# Schematics.net
KiCad netlist of a schematic drawn in EAGLE
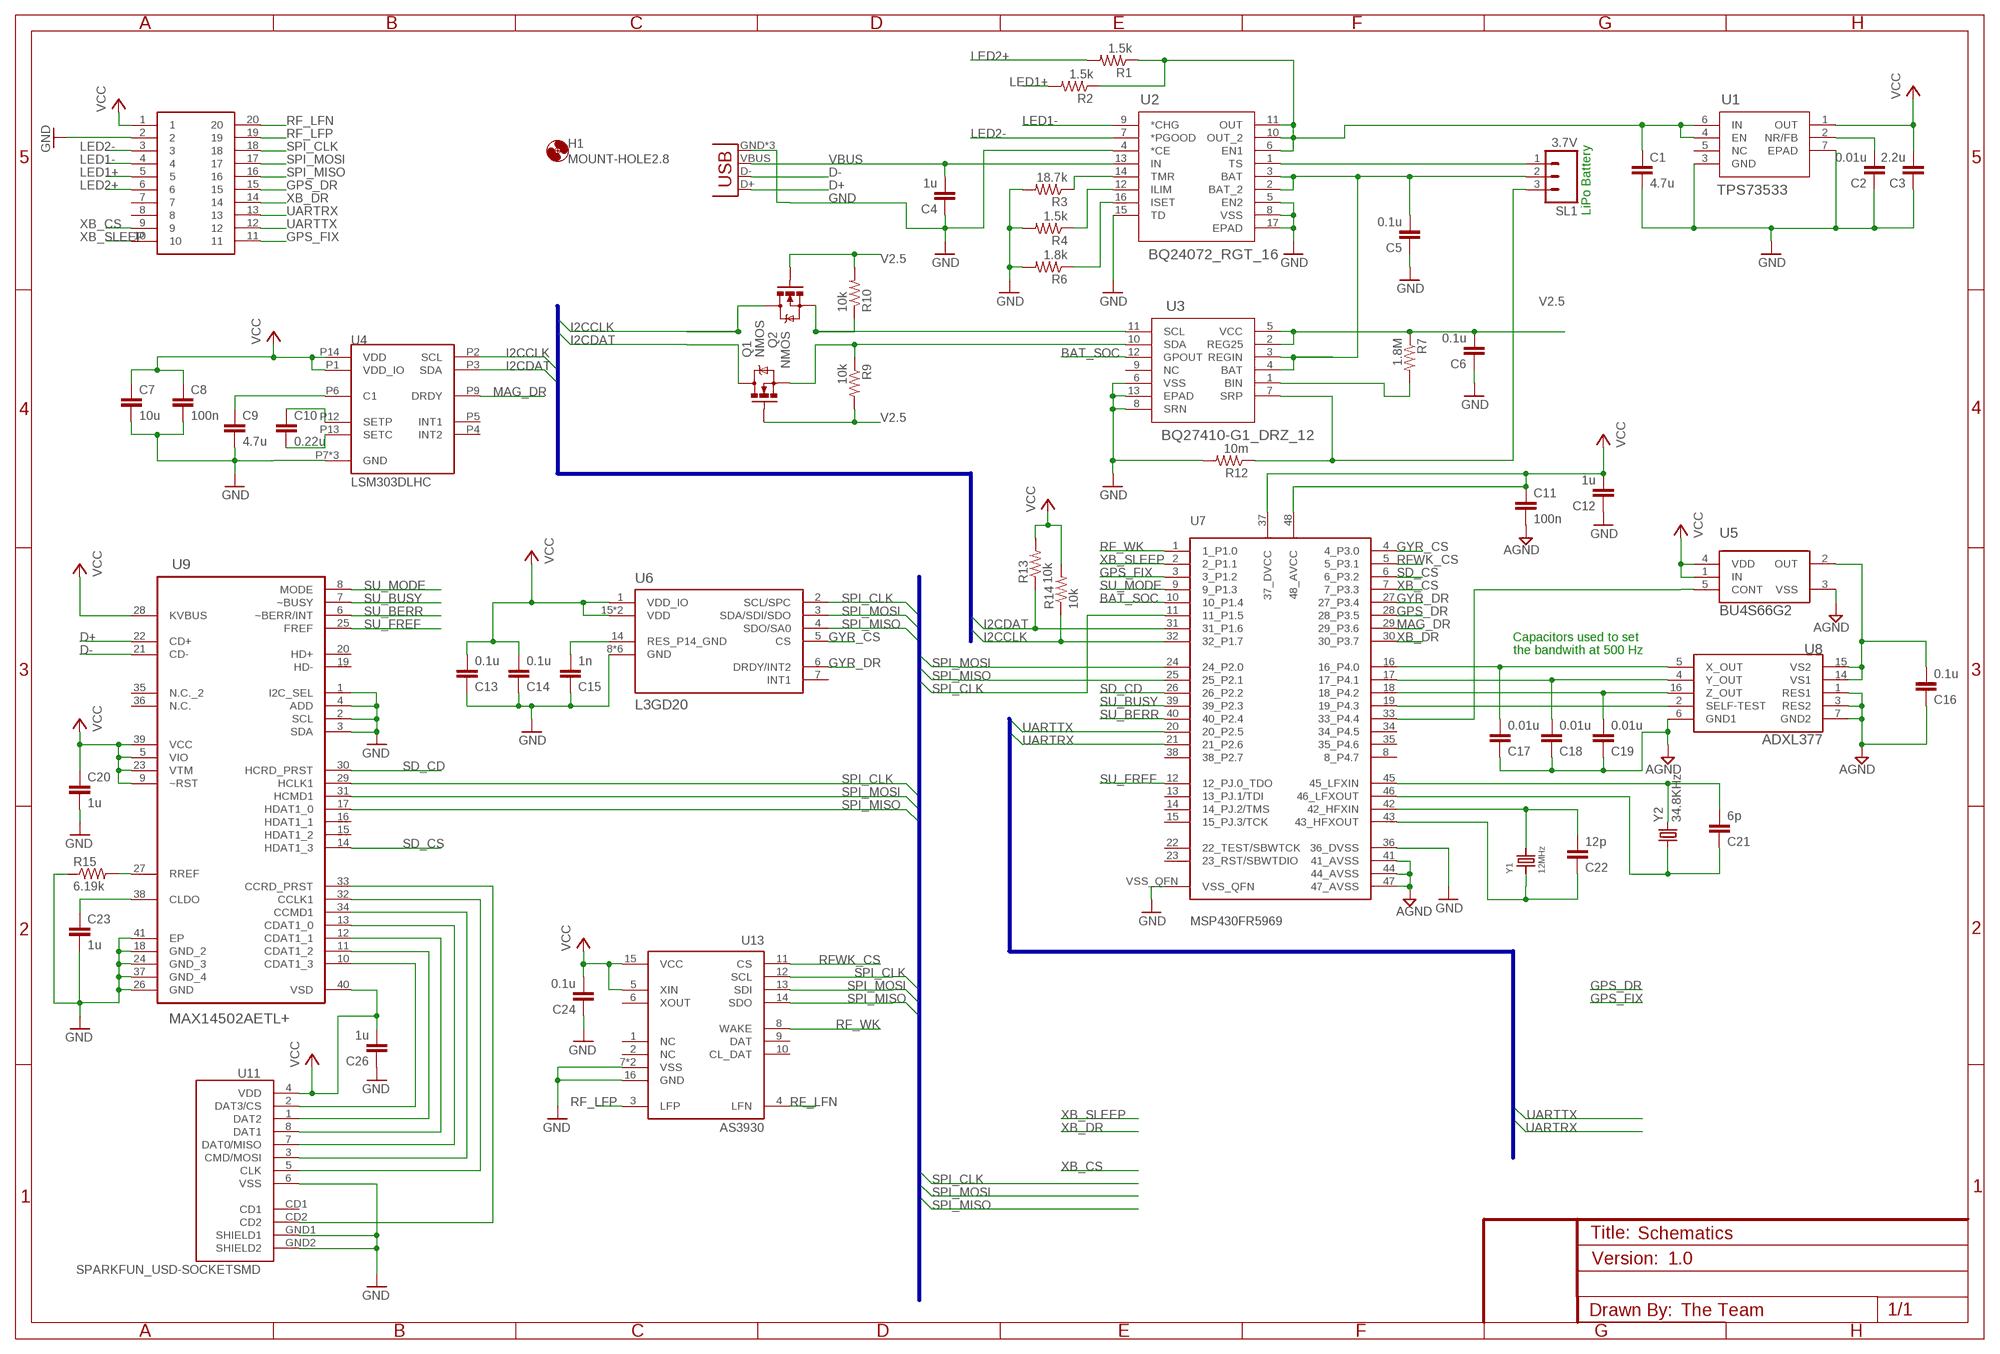
[diagram p0: schematic, sheet 1]

(export (version "E")
  (design (tool "Eeschema 10.0.6"))
  (components
    (comp (ref "C1")
      (value "4.7u")
      (footprint "eagle-import:C0603")
      (libsource (lib "eagle-import") (part "C-EUC0603"))
    )
    (comp (ref "C2")
      (value "0.01u")
      (footprint "eagle-import:C0603")
      (libsource (lib "eagle-import") (part "C-EUC0603"))
    )
    (comp (ref "C3")
      (value "2.2u")
      (footprint "eagle-import:C0603")
      (libsource (lib "eagle-import") (part "C-EUC0603"))
    )
    (comp (ref "C4")
      (value "1u")
      (footprint "eagle-import:C0603")
      (libsource (lib "eagle-import") (part "C-EUC0603"))
    )
    (comp (ref "C5")
      (value "0.1u")
      (footprint "eagle-import:C0603")
      (libsource (lib "eagle-import") (part "C-EUC0603"))
    )
    (comp (ref "C6")
      (value "0.1u")
      (footprint "eagle-import:C0603")
      (libsource (lib "eagle-import") (part "C-EUC0603"))
    )
    (comp (ref "C7")
      (value "10u")
      (footprint "eagle-import:C0603")
      (libsource (lib "eagle-import") (part "C-EUC0603"))
    )
    (comp (ref "C8")
      (value "100n")
      (footprint "eagle-import:C0603")
      (libsource (lib "eagle-import") (part "C-EUC0603"))
    )
    (comp (ref "C9")
      (value "4.7u")
      (footprint "eagle-import:C0603")
      (libsource (lib "eagle-import") (part "C-EUC0603"))
    )
    (comp (ref "C10")
      (value "0.22u")
      (footprint "eagle-import:C0603")
      (libsource (lib "eagle-import") (part "C-EUC0603"))
    )
    (comp (ref "C11")
      (value "100n")
      (footprint "eagle-import:C0603")
      (libsource (lib "eagle-import") (part "C-EUC0603"))
    )
    (comp (ref "C12")
      (value "1u")
      (footprint "eagle-import:C0603")
      (libsource (lib "eagle-import") (part "C-EUC0603"))
    )
    (comp (ref "C13")
      (value "0.1u")
      (footprint "eagle-import:C0603")
      (libsource (lib "eagle-import") (part "C-EUC0603"))
    )
    (comp (ref "C14")
      (value "0.1u")
      (footprint "eagle-import:C0603")
      (libsource (lib "eagle-import") (part "C-EUC0603"))
    )
    (comp (ref "C15")
      (value "1n")
      (footprint "eagle-import:C0603")
      (libsource (lib "eagle-import") (part "C-EUC0603"))
    )
    (comp (ref "C16")
      (value "0.1u")
      (footprint "eagle-import:C0603")
      (libsource (lib "eagle-import") (part "C-EUC0603"))
    )
    (comp (ref "C17")
      (value "0.01u")
      (footprint "eagle-import:C0603")
      (libsource (lib "eagle-import") (part "C-EUC0603"))
    )
    (comp (ref "C18")
      (value "0.01u")
      (footprint "eagle-import:C0603")
      (libsource (lib "eagle-import") (part "C-EUC0603"))
    )
    (comp (ref "C19")
      (value "0.01u")
      (footprint "eagle-import:C0603")
      (libsource (lib "eagle-import") (part "C-EUC0603"))
    )
    (comp (ref "C20")
      (value "1u")
      (footprint "eagle-import:C0603")
      (libsource (lib "eagle-import") (part "C-EUC0603"))
    )
    (comp (ref "C21")
      (value "6p")
      (footprint "eagle-import:C0603")
      (libsource (lib "eagle-import") (part "C-EUC0603"))
    )
    (comp (ref "C22")
      (value "12p")
      (footprint "eagle-import:C0603")
      (libsource (lib "eagle-import") (part "C-EUC0603"))
    )
    (comp (ref "C23")
      (value "1u")
      (footprint "eagle-import:C0603")
      (libsource (lib "eagle-import") (part "C-EUC0603"))
    )
    (comp (ref "C24")
      (value "0.1u")
      (footprint "eagle-import:C0603")
      (libsource (lib "eagle-import") (part "C-EUC0603"))
    )
    (comp (ref "C26")
      (value "1u")
      (footprint "eagle-import:C0603")
      (libsource (lib "eagle-import") (part "C-EUC0603"))
    )
    (comp (ref "H1")
      (value "MOUNT-HOLE2.8")
      (footprint "eagle-import:2,8")
      (libsource (lib "eagle-import") (part "MOUNT-HOLE2.8"))
    )
    (comp (ref "JP1")
      (value "USB-MICROB")
      (footprint "eagle-import:USB-MICROB")
      (libsource (lib "eagle-import") (part "USB-MICROB"))
    )
    (comp (ref "Q1")
      (value "NMOS")
      (footprint "eagle-import:SOT23")
      (libsource (lib "eagle-import") (part "MOSFET-NCHANNELBSS138"))
    )
    (comp (ref "Q2")
      (value "NMOS")
      (footprint "eagle-import:SOT23")
      (libsource (lib "eagle-import") (part "MOSFET-NCHANNELBSS138"))
    )
    (comp (ref "R1")
      (value "1.5k")
      (footprint "eagle-import:R0603")
      (libsource (lib "eagle-import") (part "R-US_R0603"))
    )
    (comp (ref "R2")
      (value "1.5k")
      (footprint "eagle-import:R0603")
      (libsource (lib "eagle-import") (part "R-US_R0603"))
    )
    (comp (ref "R3")
      (value "18.7k")
      (footprint "eagle-import:R0603")
      (libsource (lib "eagle-import") (part "R-US_R0603"))
    )
    (comp (ref "R4")
      (value "1.5k")
      (footprint "eagle-import:R0603")
      (libsource (lib "eagle-import") (part "R-US_R0603"))
    )
    (comp (ref "R6")
      (value "1.8k")
      (footprint "eagle-import:R0603")
      (libsource (lib "eagle-import") (part "R-US_R0603"))
    )
    (comp (ref "R7")
      (value "1.8M")
      (footprint "eagle-import:R0603")
      (libsource (lib "eagle-import") (part "R-US_R0603"))
    )
    (comp (ref "R9")
      (value "10k")
      (footprint "eagle-import:R0603")
      (libsource (lib "eagle-import") (part "R-US_R0603"))
    )
    (comp (ref "R10")
      (value "10k")
      (footprint "eagle-import:R0603")
      (libsource (lib "eagle-import") (part "R-US_R0603"))
    )
    (comp (ref "R12")
      (value "10m")
      (footprint "eagle-import:R0603")
      (libsource (lib "eagle-import") (part "R-US_R0603"))
    )
    (comp (ref "R13")
      (value "10k")
      (footprint "eagle-import:R0603")
      (libsource (lib "eagle-import") (part "R-US_R0603"))
    )
    (comp (ref "R14")
      (value "10k")
      (footprint "eagle-import:R0603")
      (libsource (lib "eagle-import") (part "R-US_R0603"))
    )
    (comp (ref "R15")
      (value "6.19k")
      (footprint "eagle-import:R0603")
      (libsource (lib "eagle-import") (part "R-US_R0603"))
    )
    (comp (ref "SL1")
      (value "3.7V")
      (footprint "eagle-import:03P")
      (libsource (lib "eagle-import") (part "M03"))
    )
    (comp (ref "U$1")
      (value "20-SOCKET")
      (footprint "eagle-import:20-SOCKET")
      (libsource (lib "eagle-import") (part "20-SOCKET"))
    )
    (comp (ref "U1")
      (value "TPS73533")
      (footprint "eagle-import:DRV6_1P6X1")
      (fields
        (field (name "MANUFACTURER") "Texas Instruments")
        (field (name "MANUFACTURER_PART_NUMBER") "tps73533_drv_6")
      )
      (libsource (lib "eagle-import") (part "TPS73533_DRV_6"))
    )
    (comp (ref "U2")
      (value "BQ24072_RGT_16")
      (footprint "eagle-import:RGT16_1P7X1P7")
      (fields
        (field (name "GENERIC_PART_NUMBER") "BQ24072")
        (field (name "MANUFACTURER") "Texas Instruments")
      )
      (libsource (lib "eagle-import") (part "BQ24072_RGT_16"))
    )
    (comp (ref "U3")
      (value "BQ27410-G1_DRZ_12")
      (footprint "eagle-import:DRZ12_1P95X2P45")
      (fields
        (field (name "GENERIC_PART_NUMBER") "BQ27410-G1")
        (field (name "MANUFACTURER") "Texas Instruments")
      )
      (libsource (lib "eagle-import") (part "BQ27410-G1_DRZ_12"))
    )
    (comp (ref "U4")
      (value "LSM303DLHC")
      (footprint "eagle-import:LGA_3X5X1_14L")
      (libsource (lib "eagle-import") (part "LSM303DLHC"))
    )
    (comp (ref "U5")
      (value "BU4S66G2")
      (footprint "eagle-import:SSOP5")
      (libsource (lib "eagle-import") (part "BU4S66G2"))
    )
    (comp (ref "U6")
      (value "L3GD20")
      (footprint "eagle-import:L3GD20")
      (libsource (lib "eagle-import") (part "L3GD20"))
    )
    (comp (ref "U7")
      (value "MSP430FR5969")
      (footprint "eagle-import:RGZ(S-PQFP-N48)")
      (libsource (lib "eagle-import") (part "MSP430FR5969"))
    )
    (comp (ref "U8")
      (value "ADXL377")
      (footprint "eagle-import:LFCSP-16")
      (libsource (lib "eagle-import") (part "ADXL377"))
    )
    (comp (ref "U9")
      (value "MAX14502AETL+")
      (footprint "eagle-import:QFN40P500X500X80-41N")
      (libsource (lib "eagle-import") (part "MAX14502AETL+"))
    )
    (comp (ref "U11")
      (value "SPARKFUN_USD-SOCKETSMD")
      (footprint "eagle-import:SPARKFUN_MICRO-SD-SOCKET-PP")
      (libsource (lib "eagle-import") (part "SPARKFUN_USD-SOCKETSMD"))
    )
    (comp (ref "U13")
      (value "AS3930")
      (footprint "eagle-import:AS3930")
      (libsource (lib "eagle-import") (part "AS3930"))
    )
    (comp (ref "Y1")
      (value "12MHz")
      (footprint "eagle-import:3.2X2.5MM")
      (libsource (lib "eagle-import") (part "CRYSTAL"))
    )
    (comp (ref "Y2")
      (value "34.8KHz")
      (footprint "eagle-import:TC38H")
      (libsource (lib "eagle-import") (part "CRYSTALTC38H"))
    )
  )
  (nets
    (net (code "1") (name "/BAT_SOC") (class "Default")
      (node (ref "U3") (pin "12") (pinfunction "GPOUT_12") (pintype "output"))
      (node (ref "U7") (pin "10") (pinfunction "10_P1.4_10") (pintype "bidirectional"))
    )
    (net (code "2") (name "/D+") (class "Default")
      (node (ref "JP1") (pin "D+") (pinfunction "D+_D+") (pintype "bidirectional"))
      (node (ref "U9") (pin "22") (pinfunction "CD+_22") (pintype "passive"))
    )
    (net (code "3") (name "/D-") (class "Default")
      (node (ref "JP1") (pin "D-") (pinfunction "D-_D-") (pintype "bidirectional"))
      (node (ref "U9") (pin "21") (pinfunction "CD-_21") (pintype "passive"))
    )
    (net (code "4") (name "/GPS_DR") (class "Default")
      (node (ref "U$1") (pin "15") (pinfunction "15_15") (pintype "bidirectional"))
      (node (ref "U7") (pin "28") (pinfunction "28_P3.5_28") (pintype "bidirectional"))
    )
    (net (code "5") (name "/GPS_FIX") (class "Default")
      (node (ref "U$1") (pin "11") (pinfunction "11_11") (pintype "bidirectional"))
      (node (ref "U7") (pin "3") (pinfunction "3_P1.2_3") (pintype "bidirectional"))
    )
    (net (code "6") (name "/GYR_CS") (class "Default")
      (node (ref "U6") (pin "5") (pinfunction "CS_5") (pintype "input"))
      (node (ref "U7") (pin "4") (pinfunction "4_P3.0_4") (pintype "bidirectional"))
    )
    (net (code "7") (name "/GYR_DR") (class "Default")
      (node (ref "U6") (pin "6") (pinfunction "DRDY/INT2_6") (pintype "output"))
      (node (ref "U7") (pin "27") (pinfunction "27_P3.4_27") (pintype "bidirectional"))
    )
    (net (code "8") (name "/I2CCLK") (class "Default")
      (node (ref "Q2") (pin "3") (pinfunction "D_3") (pintype "passive"))
      (node (ref "R14") (pin "1") (pinfunction "1_1") (pintype "passive"))
      (node (ref "U4") (pin "P2") (pinfunction "SCL_P2") (pintype "bidirectional"))
      (node (ref "U7") (pin "32") (pinfunction "32_P1.7_32") (pintype "bidirectional"))
    )
    (net (code "9") (name "/I2CDAT") (class "Default")
      (node (ref "Q1") (pin "3") (pinfunction "D_3") (pintype "passive"))
      (node (ref "R13") (pin "1") (pinfunction "1_1") (pintype "passive"))
      (node (ref "U4") (pin "P3") (pinfunction "SDA_P3") (pintype "bidirectional"))
      (node (ref "U7") (pin "31") (pinfunction "31_P1.6_31") (pintype "bidirectional"))
    )
    (net (code "10") (name "/LED1+") (class "Default")
      (node (ref "R2") (pin "2") (pinfunction "2_2") (pintype "passive"))
      (node (ref "U$1") (pin "5") (pinfunction "5_5") (pintype "bidirectional"))
    )
    (net (code "11") (name "/LED1-") (class "Default")
      (node (ref "U$1") (pin "4") (pinfunction "4_4") (pintype "bidirectional"))
      (node (ref "U2") (pin "9") (pinfunction "*CHG_9") (pintype "output"))
    )
    (net (code "12") (name "/LED2+") (class "Default")
      (node (ref "R1") (pin "2") (pinfunction "2_2") (pintype "passive"))
      (node (ref "U$1") (pin "6") (pinfunction "6_6") (pintype "bidirectional"))
    )
    (net (code "13") (name "/LED2-") (class "Default")
      (node (ref "U$1") (pin "3") (pinfunction "3_3") (pintype "bidirectional"))
      (node (ref "U2") (pin "7") (pinfunction "*PGOOD_7") (pintype "output"))
    )
    (net (code "14") (name "/MAG_DR") (class "Default")
      (node (ref "U4") (pin "P9") (pinfunction "DRDY_P9") (pintype "bidirectional"))
      (node (ref "U7") (pin "29") (pinfunction "29_P3.6_29") (pintype "bidirectional"))
    )
    (net (code "15") (name "/RFWK_CS") (class "Default")
      (node (ref "U13") (pin "11") (pinfunction "CS_11") (pintype "bidirectional"))
      (node (ref "U7") (pin "5") (pinfunction "5_P3.1_5") (pintype "bidirectional"))
    )
    (net (code "16") (name "/RF_LFN") (class "Default")
      (node (ref "U$1") (pin "20") (pinfunction "20_20") (pintype "bidirectional"))
      (node (ref "U13") (pin "4") (pinfunction "LFN_4") (pintype "bidirectional"))
    )
    (net (code "17") (name "/RF_LFP") (class "Default")
      (node (ref "U$1") (pin "19") (pinfunction "19_19") (pintype "bidirectional"))
      (node (ref "U13") (pin "3") (pinfunction "LFP_3") (pintype "bidirectional"))
    )
    (net (code "18") (name "/RF_WK") (class "Default")
      (node (ref "U13") (pin "8") (pinfunction "WAKE_8") (pintype "bidirectional"))
      (node (ref "U7") (pin "1") (pinfunction "1_P1.0_1") (pintype "bidirectional"))
    )
    (net (code "19") (name "/SD_CD") (class "Default")
      (node (ref "U7") (pin "26") (pinfunction "26_P2.2_26") (pintype "bidirectional"))
      (node (ref "U9") (pin "30") (pinfunction "HCRD_PRST_30") (pintype "passive"))
    )
    (net (code "20") (name "/SD_CS") (class "Default")
      (node (ref "U7") (pin "6") (pinfunction "6_P3.2_6") (pintype "bidirectional"))
      (node (ref "U9") (pin "14") (pinfunction "HDAT1_3_14") (pintype "passive"))
    )
    (net (code "21") (name "/SPI_CLK") (class "Default")
      (node (ref "U$1") (pin "18") (pinfunction "18_18") (pintype "bidirectional"))
      (node (ref "U13") (pin "12") (pinfunction "SCL_12") (pintype "bidirectional"))
      (node (ref "U6") (pin "2") (pinfunction "SCL/SPC_2") (pintype "input"))
      (node (ref "U7") (pin "11") (pinfunction "11_P1.5_11") (pintype "bidirectional"))
      (node (ref "U9") (pin "29") (pinfunction "HCLK1_29") (pintype "input"))
    )
    (net (code "22") (name "/SPI_MISO") (class "Default")
      (node (ref "U$1") (pin "16") (pinfunction "16_16") (pintype "bidirectional"))
      (node (ref "U13") (pin "14") (pinfunction "SDO_14") (pintype "bidirectional"))
      (node (ref "U6") (pin "4") (pinfunction "SDO/SA0_4") (pintype "bidirectional"))
      (node (ref "U7") (pin "25") (pinfunction "25_P2.1_25") (pintype "bidirectional"))
      (node (ref "U9") (pin "17") (pinfunction "HDAT1_0_17") (pintype "passive"))
    )
    (net (code "23") (name "/SPI_MOSI") (class "Default")
      (node (ref "U$1") (pin "17") (pinfunction "17_17") (pintype "bidirectional"))
      (node (ref "U13") (pin "13") (pinfunction "SDI_13") (pintype "bidirectional"))
      (node (ref "U6") (pin "3") (pinfunction "SDA/SDI/SDO_3") (pintype "bidirectional"))
      (node (ref "U7") (pin "24") (pinfunction "24_P2.0_24") (pintype "bidirectional"))
      (node (ref "U9") (pin "31") (pinfunction "HCMD1_31") (pintype "passive"))
    )
    (net (code "24") (name "/SU_BERR") (class "Default")
      (node (ref "U7") (pin "40") (pinfunction "40_P2.4_40") (pintype "bidirectional"))
      (node (ref "U9") (pin "6") (pinfunction "~{BERR/INT}_6") (pintype "bidirectional"))
    )
    (net (code "25") (name "/SU_BUSY") (class "Default")
      (node (ref "U7") (pin "39") (pinfunction "39_P2.3_39") (pintype "bidirectional"))
      (node (ref "U9") (pin "7") (pinfunction "~{BUSY}_7") (pintype "output"))
    )
    (net (code "26") (name "/SU_FREF") (class "Default")
      (node (ref "U7") (pin "12") (pinfunction "12_PJ.0_TDO_12") (pintype "bidirectional"))
      (node (ref "U9") (pin "25") (pinfunction "FREF_25") (pintype "passive"))
    )
    (net (code "27") (name "/SU_MODE") (class "Default")
      (node (ref "U7") (pin "9") (pinfunction "9_P1.3_9") (pintype "bidirectional"))
      (node (ref "U9") (pin "8") (pinfunction "MODE_8") (pintype "input"))
    )
    (net (code "28") (name "/UARTRX") (class "Default")
      (node (ref "U$1") (pin "13") (pinfunction "13_13") (pintype "bidirectional"))
      (node (ref "U7") (pin "21") (pinfunction "21_P2.6_21") (pintype "bidirectional"))
    )
    (net (code "29") (name "/UARTTX") (class "Default")
      (node (ref "U$1") (pin "12") (pinfunction "12_12") (pintype "bidirectional"))
      (node (ref "U7") (pin "20") (pinfunction "20_P2.5_20") (pintype "bidirectional"))
    )
    (net (code "30") (name "/V2.5") (class "Default")
      (node (ref "C6") (pin "2") (pinfunction "2_2") (pintype "passive"))
      (node (ref "Q1") (pin "1") (pinfunction "G_1") (pintype "passive"))
      (node (ref "Q2") (pin "1") (pinfunction "G_1") (pintype "passive"))
      (node (ref "R10") (pin "2") (pinfunction "2_2") (pintype "passive"))
      (node (ref "R7") (pin "1") (pinfunction "1_1") (pintype "passive"))
      (node (ref "R9") (pin "2") (pinfunction "2_2") (pintype "passive"))
      (node (ref "U3") (pin "2") (pinfunction "REG25_2") (pintype "power_in"))
      (node (ref "U3") (pin "5") (pinfunction "VCC_5") (pintype "power_in"))
    )
    (net (code "31") (name "/VBUS") (class "Default")
      (node (ref "C4") (pin "2") (pinfunction "2_2") (pintype "passive"))
      (node (ref "JP1") (pin "VBUS") (pinfunction "VBUS_VBUS") (pintype "bidirectional"))
      (node (ref "U2") (pin "13") (pinfunction "IN_13") (pintype "input"))
    )
    (net (code "32") (name "/XB_CS") (class "Default")
      (node (ref "U$1") (pin "9") (pinfunction "9_9") (pintype "bidirectional"))
      (node (ref "U7") (pin "7") (pinfunction "7_P3.3_7") (pintype "bidirectional"))
    )
    (net (code "33") (name "/XB_DR") (class "Default")
      (node (ref "U$1") (pin "14") (pinfunction "14_14") (pintype "bidirectional"))
      (node (ref "U7") (pin "30") (pinfunction "30_P3.7_30") (pintype "bidirectional"))
    )
    (net (code "34") (name "/XB_SLEEP") (class "Default")
      (node (ref "U$1") (pin "10") (pinfunction "10_10") (pintype "bidirectional"))
      (node (ref "U7") (pin "2") (pinfunction "2_P1.1_2") (pintype "bidirectional"))
    )
    (net (code "35") (name "AGND") (class "Default")
      (node (ref "C11") (pin "2") (pinfunction "2_2") (pintype "passive"))
      (node (ref "C16") (pin "1") (pinfunction "1_1") (pintype "passive"))
      (node (ref "C17") (pin "1") (pinfunction "1_1") (pintype "passive"))
      (node (ref "C18") (pin "1") (pinfunction "1_1") (pintype "passive"))
      (node (ref "C19") (pin "1") (pinfunction "1_1") (pintype "passive"))
      (node (ref "U5") (pin "3") (pinfunction "VSS_3") (pintype "bidirectional"))
      (node (ref "U7") (pin "41") (pinfunction "41_AVSS_41") (pintype "bidirectional"))
      (node (ref "U7") (pin "44") (pinfunction "44_AVSS_44") (pintype "bidirectional"))
      (node (ref "U7") (pin "47") (pinfunction "47_AVSS_47") (pintype "bidirectional"))
      (node (ref "U8") (pin "1") (pinfunction "RES1_1") (pintype "bidirectional"))
      (node (ref "U8") (pin "3") (pinfunction "RES2_3") (pintype "bidirectional"))
      (node (ref "U8") (pin "6") (pinfunction "GND1_6") (pintype "bidirectional"))
      (node (ref "U8") (pin "7") (pinfunction "GND2_7") (pintype "bidirectional"))
    )
    (net (code "36") (name "GND") (class "Default")
      (node (ref "C1") (pin "2") (pinfunction "2_2") (pintype "passive"))
      (node (ref "C12") (pin "1") (pinfunction "1_1") (pintype "passive"))
      (node (ref "C13") (pin "1") (pinfunction "1_1") (pintype "passive"))
      (node (ref "C14") (pin "1") (pinfunction "1_1") (pintype "passive"))
      (node (ref "C15") (pin "1") (pinfunction "1_1") (pintype "passive"))
      (node (ref "C2") (pin "1") (pinfunction "1_1") (pintype "passive"))
      (node (ref "C20") (pin "2") (pinfunction "2_2") (pintype "passive"))
      (node (ref "C23") (pin "2") (pinfunction "2_2") (pintype "passive"))
      (node (ref "C24") (pin "1") (pinfunction "1_1") (pintype "passive"))
      (node (ref "C26") (pin "1") (pinfunction "1_1") (pintype "passive"))
      (node (ref "C3") (pin "1") (pinfunction "1_1") (pintype "passive"))
      (node (ref "C4") (pin "1") (pinfunction "1_1") (pintype "passive"))
      (node (ref "C5") (pin "1") (pinfunction "1_1") (pintype "passive"))
      (node (ref "C6") (pin "1") (pinfunction "1_1") (pintype "passive"))
      (node (ref "C7") (pin "2") (pinfunction "2_2") (pintype "passive"))
      (node (ref "C8") (pin "2") (pinfunction "2_2") (pintype "passive"))
      (node (ref "C9") (pin "2") (pinfunction "2_2") (pintype "passive"))
      (node (ref "JP1") (pin "GND") (pinfunction "GND_GND") (pintype "bidirectional"))
      (node (ref "JP1") (pin "MT1") (pinfunction "GND_MT1") (pintype "bidirectional"))
      (node (ref "JP1") (pin "MT2") (pinfunction "GND_MT2") (pintype "bidirectional"))
      (node (ref "R12") (pin "2") (pinfunction "2_2") (pintype "passive"))
      (node (ref "R15") (pin "1") (pinfunction "1_1") (pintype "passive"))
      (node (ref "R3") (pin "2") (pinfunction "2_2") (pintype "passive"))
      (node (ref "R4") (pin "2") (pinfunction "2_2") (pintype "passive"))
      (node (ref "R6") (pin "2") (pinfunction "2_2") (pintype "passive"))
      (node (ref "U$1") (pin "2") (pinfunction "2_2") (pintype "bidirectional"))
      (node (ref "U1") (pin "3") (pinfunction "GND_3") (pintype "power_in"))
      (node (ref "U1") (pin "7") (pinfunction "EPAD_7") (pintype "passive"))
      (node (ref "U11") (pin "6") (pinfunction "VSS_6") (pintype "bidirectional"))
      (node (ref "U11") (pin "GND1") (pinfunction "SHIELD1_GND1") (pintype "bidirectional"))
      (node (ref "U11") (pin "GND2") (pinfunction "SHIELD2_GND2") (pintype "bidirectional"))
      (node (ref "U13") (pin "16") (pinfunction "GND_16") (pintype "bidirectional"))
      (node (ref "U13") (pin "7") (pinfunction "VSS_7") (pintype "bidirectional"))
      (node (ref "U13") (pin "EXP") (pinfunction "VSS_EXP") (pintype "bidirectional"))
      (node (ref "U2") (pin "15") (pinfunction "TD_15") (pintype "input"))
      (node (ref "U2") (pin "17") (pinfunction "EPAD_17") (pintype "power_in"))
      (node (ref "U2") (pin "4") (pinfunction "*CE_4") (pintype "input"))
      (node (ref "U2") (pin "5") (pinfunction "EN2_5") (pintype "input"))
      (node (ref "U2") (pin "8") (pinfunction "VSS_8") (pintype "power_in"))
      (node (ref "U3") (pin "13") (pinfunction "EPAD_13") (pintype "power_in"))
      (node (ref "U3") (pin "6") (pinfunction "VSS_6") (pintype "power_in"))
      (node (ref "U3") (pin "8") (pinfunction "SRN_8") (pintype "input"))
      (node (ref "U4") (pin "P10") (pinfunction "GND_P10") (pintype "bidirectional"))
      (node (ref "U4") (pin "P11") (pinfunction "GND_P11") (pintype "bidirectional"))
      (node (ref "U4") (pin "P7") (pinfunction "GND_P7") (pintype "bidirectional"))
      (node (ref "U6") (pin "10") (pinfunction "GND_10") (pintype "bidirectional"))
      (node (ref "U6") (pin "11") (pinfunction "GND_11") (pintype "bidirectional"))
      (node (ref "U6") (pin "12") (pinfunction "GND_12") (pintype "bidirectional"))
      (node (ref "U6") (pin "13") (pinfunction "GND_13") (pintype "bidirectional"))
      (node (ref "U6") (pin "8") (pinfunction "GND_8") (pintype "bidirectional"))
      (node (ref "U6") (pin "9") (pinfunction "GND_9") (pintype "bidirectional"))
      (node (ref "U7") (pin "36") (pinfunction "36_DVSS_36") (pintype "bidirectional"))
      (node (ref "U7") (pin "VSS_QFN") (pinfunction "VSS_QFN_VSS_QFN") (pintype "bidirectional"))
      (node (ref "U9") (pin "1") (pinfunction "I2C_SEL_1") (pintype "input"))
      (node (ref "U9") (pin "18") (pinfunction "GND_2_18") (pintype "passive"))
      (node (ref "U9") (pin "2") (pinfunction "SCL_2") (pintype "input"))
      (node (ref "U9") (pin "24") (pinfunction "GND_3_24") (pintype "passive"))
      (node (ref "U9") (pin "26") (pinfunction "GND_26") (pintype "passive"))
      (node (ref "U9") (pin "3") (pinfunction "SDA_3") (pintype "bidirectional"))
      (node (ref "U9") (pin "37") (pinfunction "GND_4_37") (pintype "passive"))
      (node (ref "U9") (pin "4") (pinfunction "ADD_4") (pintype "input"))
      (node (ref "U9") (pin "41") (pinfunction "EP_41") (pintype "passive"))
    )
    (net (code "37") (name "Net-(Q1-S)") (class "Default")
      (node (ref "Q1") (pin "2") (pinfunction "S_2") (pintype "passive"))
      (node (ref "R9") (pin "1") (pinfunction "1_1") (pintype "passive"))
      (node (ref "U3") (pin "10") (pinfunction "SDA_10") (pintype "bidirectional"))
    )
    (net (code "38") (name "Net-(Q2-S)") (class "Default")
      (node (ref "Q2") (pin "2") (pinfunction "S_2") (pintype "passive"))
      (node (ref "R10") (pin "1") (pinfunction "1_1") (pintype "passive"))
      (node (ref "U3") (pin "11") (pinfunction "SCL_11") (pintype "input"))
    )
    (net (code "39") (name "Net-(U1-EN)") (class "Default")
      (node (ref "C1") (pin "1") (pinfunction "1_1") (pintype "passive"))
      (node (ref "R1") (pin "1") (pinfunction "1_1") (pintype "passive"))
      (node (ref "R2") (pin "1") (pinfunction "1_1") (pintype "passive"))
      (node (ref "U1") (pin "4") (pinfunction "EN_4") (pintype "passive"))
      (node (ref "U1") (pin "6") (pinfunction "IN_6") (pintype "input"))
      (node (ref "U2") (pin "10") (pinfunction "OUT_2_10") (pintype "output"))
      (node (ref "U2") (pin "11") (pinfunction "OUT_11") (pintype "output"))
      (node (ref "U2") (pin "6") (pinfunction "EN1_6") (pintype "input"))
    )
    (net (code "40") (name "Net-(U1-NR{slash}FB)") (class "Default")
      (node (ref "C2") (pin "2") (pinfunction "2_2") (pintype "passive"))
      (node (ref "U1") (pin "2") (pinfunction "NR/FB_2") (pintype "bidirectional"))
    )
    (net (code "41") (name "Net-(U2-BAT)") (class "Default")
      (node (ref "C5") (pin "2") (pinfunction "2_2") (pintype "passive"))
      (node (ref "SL1") (pin "2") (pinfunction "2_2") (pintype "passive"))
      (node (ref "U2") (pin "2") (pinfunction "BAT_2_2") (pintype "bidirectional"))
      (node (ref "U2") (pin "3") (pinfunction "BAT_3") (pintype "bidirectional"))
      (node (ref "U3") (pin "3") (pinfunction "REGIN_3") (pintype "power_in"))
      (node (ref "U3") (pin "4") (pinfunction "BAT_4") (pintype "input"))
    )
    (net (code "42") (name "Net-(U2-ILIM)") (class "Default")
      (node (ref "R4") (pin "1") (pinfunction "1_1") (pintype "passive"))
      (node (ref "U2") (pin "12") (pinfunction "ILIM_12") (pintype "input"))
    )
    (net (code "43") (name "Net-(U2-ISET)") (class "Default")
      (node (ref "R6") (pin "1") (pinfunction "1_1") (pintype "passive"))
      (node (ref "U2") (pin "16") (pinfunction "ISET_16") (pintype "bidirectional"))
    )
    (net (code "44") (name "Net-(U2-TMR)") (class "Default")
      (node (ref "R3") (pin "1") (pinfunction "1_1") (pintype "passive"))
      (node (ref "U2") (pin "14") (pinfunction "TMR_14") (pintype "input"))
    )
    (net (code "45") (name "Net-(U2-TS)") (class "Default")
      (node (ref "SL1") (pin "1") (pinfunction "1_1") (pintype "passive"))
      (node (ref "U2") (pin "1") (pinfunction "TS_1") (pintype "input"))
    )
    (net (code "46") (name "Net-(U3-BIN)") (class "Default")
      (node (ref "R7") (pin "2") (pinfunction "2_2") (pintype "passive"))
      (node (ref "U3") (pin "1") (pinfunction "BIN_1") (pintype "input"))
    )
    (net (code "47") (name "Net-(U3-SRP)") (class "Default")
      (node (ref "R12") (pin "1") (pinfunction "1_1") (pintype "passive"))
      (node (ref "SL1") (pin "3") (pinfunction "3_3") (pintype "passive"))
      (node (ref "U3") (pin "7") (pinfunction "SRP_7") (pintype "input"))
    )
    (net (code "48") (name "Net-(U4-C1)") (class "Default")
      (node (ref "C9") (pin "1") (pinfunction "1_1") (pintype "passive"))
      (node (ref "U4") (pin "P6") (pinfunction "C1_P6") (pintype "bidirectional"))
    )
    (net (code "49") (name "Net-(U4-SETC)") (class "Default")
      (node (ref "C10") (pin "2") (pinfunction "2_2") (pintype "passive"))
      (node (ref "U4") (pin "P13") (pinfunction "SETC_P13") (pintype "bidirectional"))
    )
    (net (code "50") (name "Net-(U4-SETP)") (class "Default")
      (node (ref "C10") (pin "1") (pinfunction "1_1") (pintype "passive"))
      (node (ref "U4") (pin "P12") (pinfunction "SETP_P12") (pintype "bidirectional"))
    )
    (net (code "51") (name "Net-(U5-CONT)") (class "Default")
      (node (ref "U5") (pin "5") (pinfunction "CONT_5") (pintype "bidirectional"))
      (node (ref "U7") (pin "33") (pinfunction "33_P4.4_33") (pintype "bidirectional"))
    )
    (net (code "52") (name "Net-(U5-OUT)") (class "Default")
      (node (ref "C16") (pin "2") (pinfunction "2_2") (pintype "passive"))
      (node (ref "U5") (pin "2") (pinfunction "OUT_2") (pintype "bidirectional"))
      (node (ref "U8") (pin "14") (pinfunction "VS1_14") (pintype "bidirectional"))
      (node (ref "U8") (pin "15") (pinfunction "VS2_15") (pintype "bidirectional"))
    )
    (net (code "53") (name "Net-(U6-RES_P14_GND)") (class "Default")
      (node (ref "C15") (pin "2") (pinfunction "2_2") (pintype "passive"))
      (node (ref "U6") (pin "14") (pinfunction "RES_P14_GND_14") (pintype "bidirectional"))
    )
    (net (code "54") (name "Net-(U7-16_P4.0)") (class "Default")
      (node (ref "C17") (pin "2") (pinfunction "2_2") (pintype "passive"))
      (node (ref "U7") (pin "16") (pinfunction "16_P4.0_16") (pintype "bidirectional"))
      (node (ref "U8") (pin "5") (pinfunction "X_OUT_5") (pintype "bidirectional"))
    )
    (net (code "55") (name "Net-(U7-17_P4.1)") (class "Default")
      (node (ref "C18") (pin "2") (pinfunction "2_2") (pintype "passive"))
      (node (ref "U7") (pin "17") (pinfunction "17_P4.1_17") (pintype "bidirectional"))
      (node (ref "U8") (pin "4") (pinfunction "Y_OUT_4") (pintype "bidirectional"))
    )
    (net (code "56") (name "Net-(U7-18_P4.2)") (class "Default")
      (node (ref "C19") (pin "2") (pinfunction "2_2") (pintype "passive"))
      (node (ref "U7") (pin "18") (pinfunction "18_P4.2_18") (pintype "bidirectional"))
      (node (ref "U8") (pin "16") (pinfunction "Z_OUT_16") (pintype "bidirectional"))
    )
    (net (code "57") (name "Net-(U7-19_P4.3)") (class "Default")
      (node (ref "U7") (pin "19") (pinfunction "19_P4.3_19") (pintype "bidirectional"))
      (node (ref "U8") (pin "2") (pinfunction "SELF-TEST_2") (pintype "bidirectional"))
    )
    (net (code "58") (name "Net-(U7-42_HFXIN)") (class "Default")
      (node (ref "C22") (pin "2") (pinfunction "2_2") (pintype "passive"))
      (node (ref "U7") (pin "42") (pinfunction "42_HFXIN_42") (pintype "bidirectional"))
      (node (ref "Y1") (pin "P$3") (pinfunction "2_P$3") (pintype "passive"))
    )
    (net (code "59") (name "Net-(U7-43_HFXOUT)") (class "Default")
      (node (ref "C22") (pin "1") (pinfunction "1_1") (pintype "passive"))
      (node (ref "U7") (pin "43") (pinfunction "43_HFXOUT_43") (pintype "bidirectional"))
      (node (ref "Y1") (pin "P$1") (pinfunction "1_P$1") (pintype "passive"))
    )
    (net (code "60") (name "Net-(U7-45_LFXIN)") (class "Default")
      (node (ref "C21") (pin "2") (pinfunction "2_2") (pintype "passive"))
      (node (ref "U7") (pin "45") (pinfunction "45_LFXIN_45") (pintype "bidirectional"))
      (node (ref "Y2") (pin "2") (pinfunction "2_2") (pintype "passive"))
    )
    (net (code "61") (name "Net-(U7-46_LFXOUT)") (class "Default")
      (node (ref "C21") (pin "1") (pinfunction "1_1") (pintype "passive"))
      (node (ref "U7") (pin "46") (pinfunction "46_LFXOUT_46") (pintype "bidirectional"))
      (node (ref "Y2") (pin "1") (pinfunction "1_1") (pintype "passive"))
    )
    (net (code "62") (name "Net-(U9-CCRD_PRST)") (class "Default")
      (node (ref "U11") (pin "CD2") (pinfunction "CD2_CD2") (pintype "bidirectional"))
      (node (ref "U9") (pin "33") (pinfunction "CCRD_PRST_33") (pintype "passive"))
    )
    (net (code "63") (name "Net-(U9-CLDO)") (class "Default")
      (node (ref "C23") (pin "1") (pinfunction "1_1") (pintype "passive"))
      (node (ref "U9") (pin "38") (pinfunction "CLDO_38") (pintype "power_in"))
    )
    (net (code "64") (name "Net-(U9-RREF)") (class "Default")
      (node (ref "R15") (pin "2") (pinfunction "2_2") (pintype "passive"))
      (node (ref "U9") (pin "27") (pinfunction "RREF_27") (pintype "passive"))
    )
    (net (code "65") (name "Net-(U11-CLK)") (class "Default")
      (node (ref "U11") (pin "5") (pinfunction "CLK_5") (pintype "bidirectional"))
      (node (ref "U9") (pin "32") (pinfunction "CCLK1_32") (pintype "input"))
    )
    (net (code "66") (name "Net-(U11-CMD{slash}MOSI)") (class "Default")
      (node (ref "U11") (pin "3") (pinfunction "CMD/MOSI_3") (pintype "bidirectional"))
      (node (ref "U9") (pin "34") (pinfunction "CCMD1_34") (pintype "passive"))
    )
    (net (code "67") (name "Net-(U11-DAT0{slash}MISO)") (class "Default")
      (node (ref "U11") (pin "7") (pinfunction "DAT0/MISO_7") (pintype "bidirectional"))
      (node (ref "U9") (pin "13") (pinfunction "CDAT1_0_13") (pintype "passive"))
    )
    (net (code "68") (name "Net-(U11-DAT1)") (class "Default")
      (node (ref "U11") (pin "8") (pinfunction "DAT1_8") (pintype "bidirectional"))
      (node (ref "U9") (pin "12") (pinfunction "CDAT1_1_12") (pintype "passive"))
    )
    (net (code "69") (name "Net-(U11-DAT2)") (class "Default")
      (node (ref "U11") (pin "1") (pinfunction "DAT2_1") (pintype "bidirectional"))
      (node (ref "U9") (pin "11") (pinfunction "CDAT1_2_11") (pintype "passive"))
    )
    (net (code "70") (name "Net-(U11-DAT3{slash}CS)") (class "Default")
      (node (ref "U11") (pin "2") (pinfunction "DAT3/CS_2") (pintype "bidirectional"))
      (node (ref "U9") (pin "10") (pinfunction "CDAT1_3_10") (pintype "passive"))
    )
    (net (code "71") (name "VCC") (class "Default")
      (node (ref "C11") (pin "1") (pinfunction "1_1") (pintype "passive"))
      (node (ref "C12") (pin "2") (pinfunction "2_2") (pintype "passive"))
      (node (ref "C13") (pin "2") (pinfunction "2_2") (pintype "passive"))
      (node (ref "C14") (pin "2") (pinfunction "2_2") (pintype "passive"))
      (node (ref "C20") (pin "1") (pinfunction "1_1") (pintype "passive"))
      (node (ref "C24") (pin "2") (pinfunction "2_2") (pintype "passive"))
      (node (ref "C26") (pin "2") (pinfunction "2_2") (pintype "passive"))
      (node (ref "C3") (pin "2") (pinfunction "2_2") (pintype "passive"))
      (node (ref "C7") (pin "1") (pinfunction "1_1") (pintype "passive"))
      (node (ref "C8") (pin "1") (pinfunction "1_1") (pintype "passive"))
      (node (ref "R13") (pin "2") (pinfunction "2_2") (pintype "passive"))
      (node (ref "R14") (pin "2") (pinfunction "2_2") (pintype "passive"))
      (node (ref "U$1") (pin "1") (pinfunction "1_1") (pintype "bidirectional"))
      (node (ref "U1") (pin "1") (pinfunction "OUT_1") (pintype "power_in"))
      (node (ref "U11") (pin "4") (pinfunction "VDD_4") (pintype "bidirectional"))
      (node (ref "U13") (pin "15") (pinfunction "VCC_15") (pintype "bidirectional"))
      (node (ref "U13") (pin "5") (pinfunction "XIN_5") (pintype "bidirectional"))
      (node (ref "U4") (pin "P1") (pinfunction "VDD_IO_P1") (pintype "bidirectional"))
      (node (ref "U4") (pin "P14") (pinfunction "VDD_P14") (pintype "bidirectional"))
      (node (ref "U5") (pin "1") (pinfunction "IN_1") (pintype "bidirectional"))
      (node (ref "U5") (pin "4") (pinfunction "VDD_4") (pintype "bidirectional"))
      (node (ref "U6") (pin "1") (pinfunction "VDD_IO_1") (pintype "bidirectional"))
      (node (ref "U6") (pin "15") (pinfunction "VDD_15") (pintype "bidirectional"))
      (node (ref "U6") (pin "16") (pinfunction "VDD_16") (pintype "bidirectional"))
      (node (ref "U7") (pin "37") (pinfunction "37_DVCC_37") (pintype "bidirectional"))
      (node (ref "U7") (pin "48") (pinfunction "48_AVCC_48") (pintype "bidirectional"))
      (node (ref "U9") (pin "23") (pinfunction "VTM_23") (pintype "passive"))
      (node (ref "U9") (pin "28") (pinfunction "KVBUS_28") (pintype "passive"))
      (node (ref "U9") (pin "39") (pinfunction "VCC_39") (pintype "power_in"))
      (node (ref "U9") (pin "40") (pinfunction "VSD_40") (pintype "power_in"))
      (node (ref "U9") (pin "5") (pinfunction "VIO_5") (pintype "passive"))
      (node (ref "U9") (pin "9") (pinfunction "~{RST}_9") (pintype "input"))
    )
    (net (code "72") (name "unconnected-(U$1-Pad7)") (class "Default")
      (node (ref "U$1") (pin "7") (pinfunction "7_7") (pintype "bidirectional"))
    )
    (net (code "73") (name "unconnected-(U$1-Pad8)") (class "Default")
      (node (ref "U$1") (pin "8") (pinfunction "8_8") (pintype "bidirectional"))
    )
    (net (code "74") (name "unconnected-(U1-NC-Pad5)") (class "Default")
      (node (ref "U1") (pin "5") (pinfunction "NC_5") (pintype "passive"))
    )
    (net (code "75") (name "unconnected-(U3-NC-Pad9)") (class "Default")
      (node (ref "U3") (pin "9") (pinfunction "NC_9") (pintype "no_connect"))
    )
    (net (code "76") (name "unconnected-(U4-INT1-PadP5)") (class "Default")
      (node (ref "U4") (pin "P5") (pinfunction "INT1_P5") (pintype "bidirectional"))
    )
    (net (code "77") (name "unconnected-(U4-INT2-PadP4)") (class "Default")
      (node (ref "U4") (pin "P4") (pinfunction "INT2_P4") (pintype "bidirectional"))
    )
    (net (code "78") (name "unconnected-(U6-INT1-Pad7)") (class "Default")
      (node (ref "U6") (pin "7") (pinfunction "INT1_7") (pintype "output"))
    )
    (net (code "79") (name "unconnected-(U7-8_P4.7-Pad8)") (class "Default")
      (node (ref "U7") (pin "8") (pinfunction "8_P4.7_8") (pintype "bidirectional"))
    )
    (net (code "80") (name "unconnected-(U7-13_PJ.1{slash}TDI-Pad13)") (class "Default")
      (node (ref "U7") (pin "13") (pinfunction "13_PJ.1/TDI_13") (pintype "bidirectional"))
    )
    (net (code "81") (name "unconnected-(U7-14_PJ.2{slash}TMS-Pad14)") (class "Default")
      (node (ref "U7") (pin "14") (pinfunction "14_PJ.2/TMS_14") (pintype "bidirectional"))
    )
    (net (code "82") (name "unconnected-(U7-15_PJ.3{slash}TCK-Pad15)") (class "Default")
      (node (ref "U7") (pin "15") (pinfunction "15_PJ.3/TCK_15") (pintype "bidirectional"))
    )
    (net (code "83") (name "unconnected-(U7-22_TEST{slash}SBWTCK-Pad22)") (class "Default")
      (node (ref "U7") (pin "22") (pinfunction "22_TEST/SBWTCK_22") (pintype "bidirectional"))
    )
    (net (code "84") (name "unconnected-(U7-23_RST{slash}SBWTDIO-Pad23)") (class "Default")
      (node (ref "U7") (pin "23") (pinfunction "23_RST/SBWTDIO_23") (pintype "bidirectional"))
    )
    (net (code "85") (name "unconnected-(U7-34_P4.5-Pad34)") (class "Default")
      (node (ref "U7") (pin "34") (pinfunction "34_P4.5_34") (pintype "bidirectional"))
    )
    (net (code "86") (name "unconnected-(U7-35_P4.6-Pad35)") (class "Default")
      (node (ref "U7") (pin "35") (pinfunction "35_P4.6_35") (pintype "bidirectional"))
    )
    (net (code "87") (name "unconnected-(U7-38_P2.7-Pad38)") (class "Default")
      (node (ref "U7") (pin "38") (pinfunction "38_P2.7_38") (pintype "bidirectional"))
    )
    (net (code "88") (name "unconnected-(U9-HD+-Pad20)") (class "Default")
      (node (ref "U9") (pin "20") (pinfunction "HD+_20") (pintype "passive"))
    )
    (net (code "89") (name "unconnected-(U9-HD--Pad19)") (class "Default")
      (node (ref "U9") (pin "19") (pinfunction "HD-_19") (pintype "passive"))
    )
    (net (code "90") (name "unconnected-(U9-HDAT1_1-Pad16)") (class "Default")
      (node (ref "U9") (pin "16") (pinfunction "HDAT1_1_16") (pintype "passive"))
    )
    (net (code "91") (name "unconnected-(U9-HDAT1_2-Pad15)") (class "Default")
      (node (ref "U9") (pin "15") (pinfunction "HDAT1_2_15") (pintype "passive"))
    )
    (net (code "92") (name "unconnected-(U9-N.C.-Pad36)") (class "Default")
      (node (ref "U9") (pin "36") (pinfunction "N.C._36") (pintype "no_connect"))
    )
    (net (code "93") (name "unconnected-(U9-N.C._2-Pad35)") (class "Default")
      (node (ref "U9") (pin "35") (pinfunction "N.C._2_35") (pintype "no_connect"))
    )
    (net (code "94") (name "unconnected-(U11-PadCD1)") (class "Default")
      (node (ref "U11") (pin "CD1") (pinfunction "CD1_CD1") (pintype "bidirectional"))
    )
    (net (code "95") (name "unconnected-(U13-CL_DAT-Pad10)") (class "Default")
      (node (ref "U13") (pin "10") (pinfunction "CL_DAT_10") (pintype "bidirectional"))
    )
    (net (code "96") (name "unconnected-(U13-DAT-Pad9)") (class "Default")
      (node (ref "U13") (pin "9") (pinfunction "DAT_9") (pintype "bidirectional"))
    )
    (net (code "97") (name "unconnected-(U13-NC-Pad1)") (class "Default")
      (node (ref "U13") (pin "1") (pinfunction "NC_1") (pintype "bidirectional"))
    )
    (net (code "98") (name "unconnected-(U13-NC-Pad2)") (class "Default")
      (node (ref "U13") (pin "2") (pinfunction "NC_2") (pintype "bidirectional"))
    )
    (net (code "99") (name "unconnected-(U13-XOUT-Pad6)") (class "Default")
      (node (ref "U13") (pin "6") (pinfunction "XOUT_6") (pintype "bidirectional"))
    )
  )
)
